# b.net
KiCad netlist of a schematic drawn in EAGLE
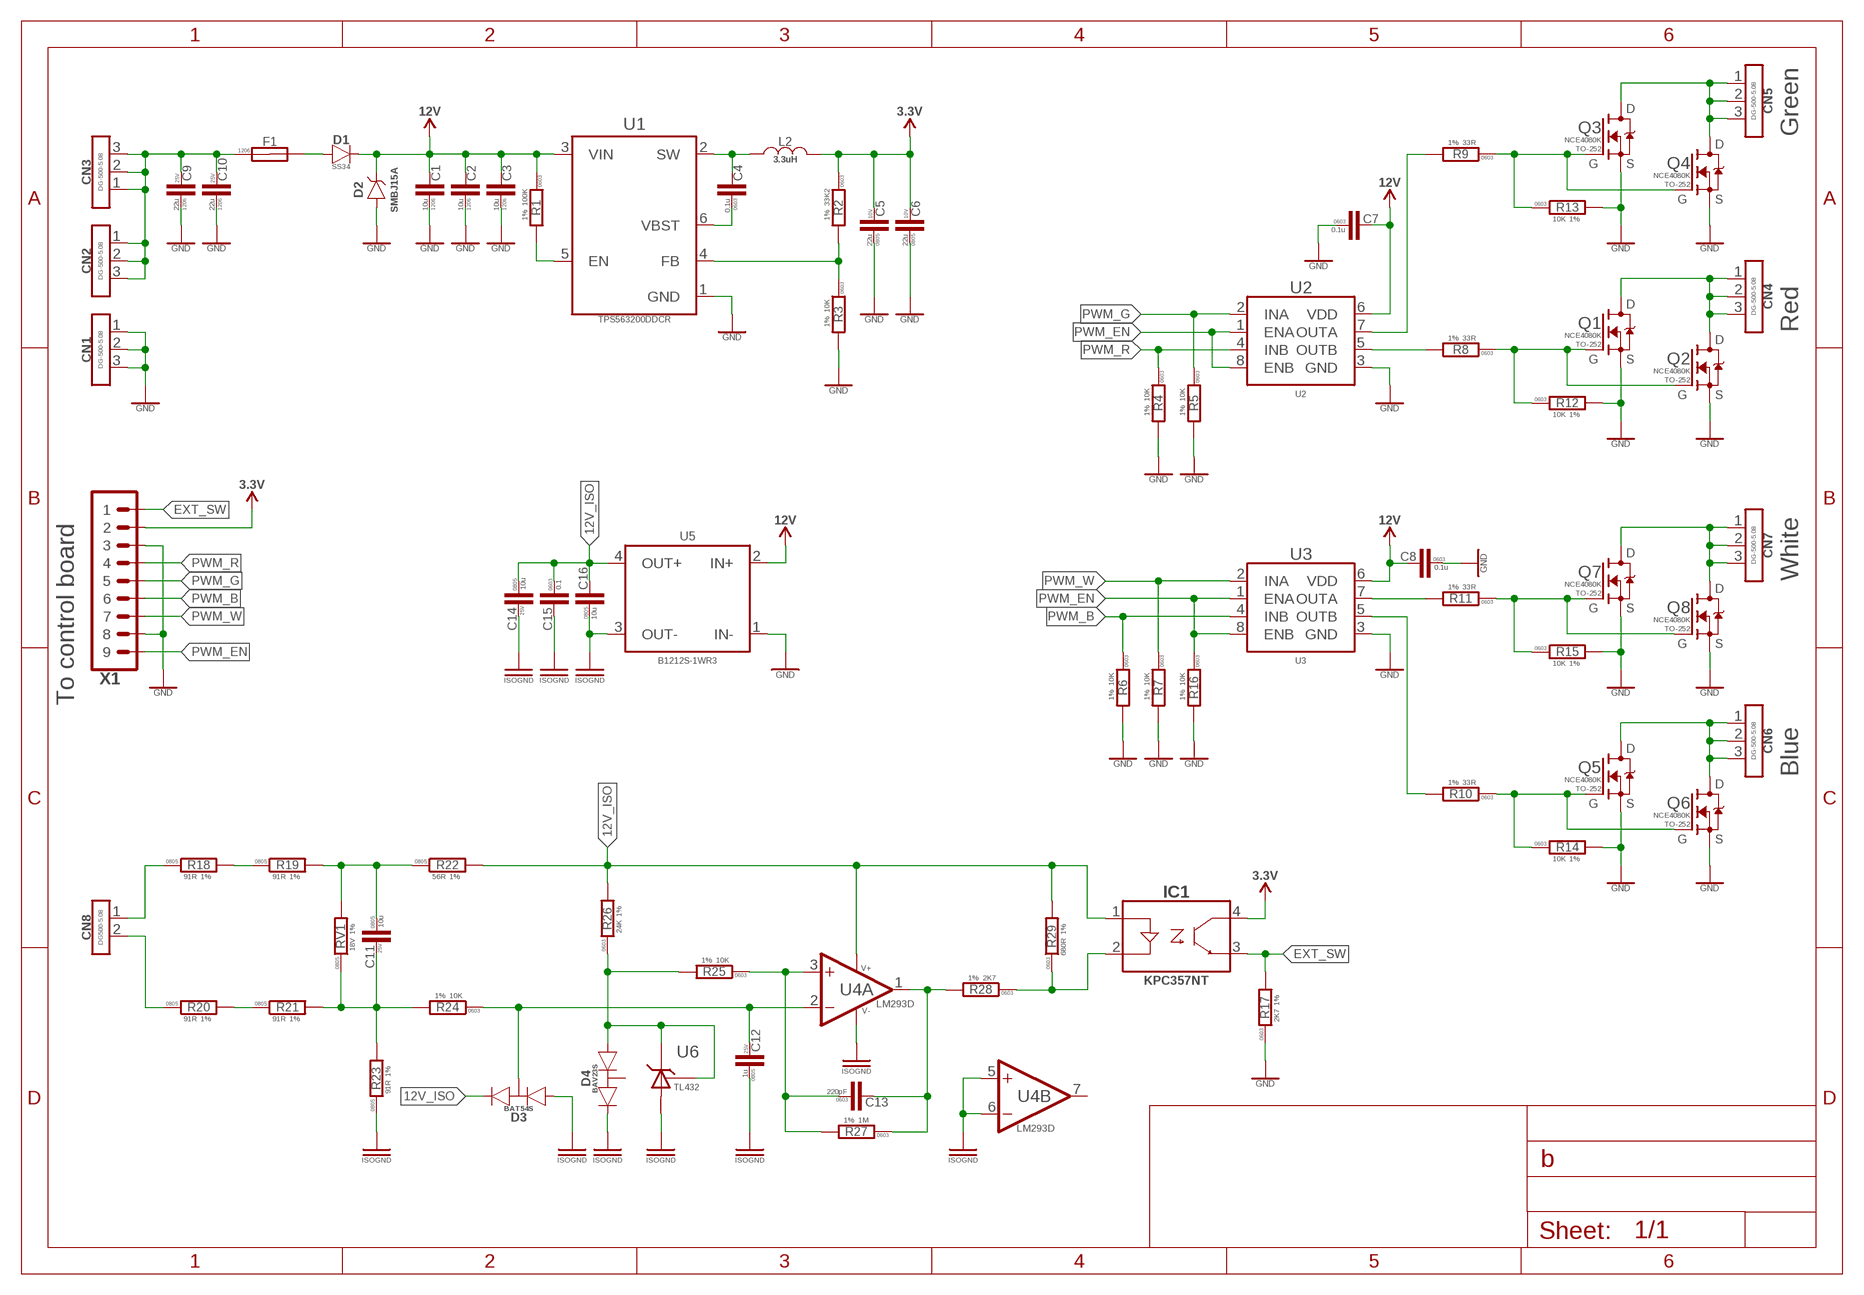
[diagram p0: schematic, sheet 1]

(export (version "E")
  (design (tool "Eeschema 10.0.6"))
  (components
    (comp (ref "C1")
      (value "10u")
      (footprint "eagle-import:C1206")
      (fields (field (name "PACKAGE") "1206"))
      (libsource (lib "eagle-import") (part "C-1206"))
    )
    (comp (ref "C2")
      (value "10u")
      (footprint "eagle-import:C1206")
      (fields (field (name "PACKAGE") "1206"))
      (libsource (lib "eagle-import") (part "C-1206"))
    )
    (comp (ref "C3")
      (value "10u")
      (footprint "eagle-import:C1206")
      (fields (field (name "PACKAGE") "1206"))
      (libsource (lib "eagle-import") (part "C-1206"))
    )
    (comp (ref "C4")
      (value "0.1u")
      (footprint "eagle-import:C0603")
      (fields (field (name "PACKAGE") "0603"))
      (libsource (lib "eagle-import") (part "C-0603"))
    )
    (comp (ref "C5")
      (value "22u")
      (footprint "eagle-import:C0805")
      (fields (field (name "PACKAGE") "0805") (field (name "VOLTAGE") "10V"))
      (libsource (lib "eagle-import") (part "C-0805"))
    )
    (comp (ref "C6")
      (value "22u")
      (footprint "eagle-import:C0805")
      (fields (field (name "PACKAGE") "0805") (field (name "VOLTAGE") "10V"))
      (libsource (lib "eagle-import") (part "C-0805"))
    )
    (comp (ref "C7")
      (value "0.1u")
      (footprint "eagle-import:C0603")
      (fields (field (name "PACKAGE") "0603"))
      (libsource (lib "eagle-import") (part "C-0603"))
    )
    (comp (ref "C8")
      (value "0.1u")
      (footprint "eagle-import:C0603")
      (fields (field (name "PACKAGE") "0603"))
      (libsource (lib "eagle-import") (part "C-0603"))
    )
    (comp (ref "C9")
      (value "22u")
      (footprint "eagle-import:C1206")
      (fields (field (name "PACKAGE") "1206") (field (name "VOLTAGE") "25V"))
      (libsource (lib "eagle-import") (part "C-1206"))
    )
    (comp (ref "C10")
      (value "22u")
      (footprint "eagle-import:C1206")
      (fields (field (name "PACKAGE") "1206") (field (name "VOLTAGE") "25V"))
      (libsource (lib "eagle-import") (part "C-1206"))
    )
    (comp (ref "C11")
      (value "10u")
      (footprint "eagle-import:C0805")
      (fields (field (name "PACKAGE") "0805") (field (name "VOLTAGE") "25V"))
      (libsource (lib "eagle-import") (part "C-0805"))
    )
    (comp (ref "C12")
      (value "1u")
      (footprint "eagle-import:C0805")
      (fields (field (name "PACKAGE") "0805") (field (name "VOLTAGE") "25V"))
      (libsource (lib "eagle-import") (part "C-0805"))
    )
    (comp (ref "C13")
      (value "220pF")
      (footprint "eagle-import:C0603")
      (fields (field (name "PACKAGE") "0603"))
      (libsource (lib "eagle-import") (part "C-0603"))
    )
    (comp (ref "C14")
      (value "10u")
      (footprint "eagle-import:C0805")
      (fields (field (name "PACKAGE") "0805") (field (name "VOLTAGE") "25V"))
      (libsource (lib "eagle-import") (part "C-0805"))
    )
    (comp (ref "C15")
      (value "0.1")
      (footprint "eagle-import:C0603")
      (fields (field (name "PACKAGE") "0603"))
      (libsource (lib "eagle-import") (part "C-0603"))
    )
    (comp (ref "C16")
      (value "10u")
      (footprint "eagle-import:C0805")
      (fields (field (name "PACKAGE") "0805"))
      (libsource (lib "eagle-import") (part "C-0805"))
    )
    (comp (ref "CN1")
      (value "CON-3P-DG500-5.08")
      (footprint "eagle-import:DG500-5.08-03P")
      (fields (field (name "TYPE") "DG-500-5.08") (field (name "MANF") "Degson Electronics"))
      (libsource (lib "eagle-import") (part "CON-3P-DG500-5.08"))
    )
    (comp (ref "CN2")
      (value "CON-3P-DG500-5.08")
      (footprint "eagle-import:DG500-5.08-03P")
      (fields (field (name "TYPE") "DG-500-5.08") (field (name "MANF") "Degson Electronics"))
      (libsource (lib "eagle-import") (part "CON-3P-DG500-5.08"))
    )
    (comp (ref "CN3")
      (value "CON-3P-DG500-5.08")
      (footprint "eagle-import:DG500-5.08-03P")
      (fields (field (name "TYPE") "DG-500-5.08") (field (name "MANF") "Degson Electronics"))
      (libsource (lib "eagle-import") (part "CON-3P-DG500-5.08"))
    )
    (comp (ref "CN4")
      (value "CON-3P-DG500-5.08")
      (footprint "eagle-import:DG500-5.08-03P")
      (fields (field (name "TYPE") "DG-500-5.08") (field (name "MANF") "Degson Electronics"))
      (libsource (lib "eagle-import") (part "CON-3P-DG500-5.08"))
    )
    (comp (ref "CN5")
      (value "CON-3P-DG500-5.08")
      (footprint "eagle-import:DG500-5.08-03P")
      (fields (field (name "TYPE") "DG-500-5.08") (field (name "MANF") "Degson Electronics"))
      (libsource (lib "eagle-import") (part "CON-3P-DG500-5.08"))
    )
    (comp (ref "CN6")
      (value "CON-3P-DG500-5.08")
      (footprint "eagle-import:DG500-5.08-03P")
      (fields (field (name "TYPE") "DG-500-5.08") (field (name "MANF") "Degson Electronics"))
      (libsource (lib "eagle-import") (part "CON-3P-DG500-5.08"))
    )
    (comp (ref "CN7")
      (value "CON-3P-DG500-5.08")
      (footprint "eagle-import:DG500-5.08-03P")
      (fields (field (name "TYPE") "DG-500-5.08") (field (name "MANF") "Degson Electronics"))
      (libsource (lib "eagle-import") (part "CON-3P-DG500-5.08"))
    )
    (comp (ref "CN8")
      (value "DG508V-2P")
      (footprint "eagle-import:DG500-5.08-02P")
      (fields (field (name "TYPE") "DG500-5.08") (field (name "MANF") "Degson Electronics"))
      (libsource (lib "eagle-import") (part "CON-2P-DG500-5.08"))
    )
    (comp (ref "D1")
      (value "SS24")
      (footprint "eagle-import:DO-214AC(SMA)")
      (fields (field (name "MANF#") "SS34") (field (name "MANF") "MDD（Microdiode Electronics）"))
      (libsource (lib "eagle-import") (part "SS34"))
    )
    (comp (ref "D2")
      (value "SMBJ15A-SMB")
      (footprint "eagle-import:DO-214AA(SMB)")
      (fields (field (name "MANF#") "SMBJ15A") (field (name "MANF") "Littelfuse"))
      (libsource (lib "eagle-import") (part "SMBJ15A-SMB"))
    )
    (comp (ref "D3")
      (value "BAT54S")
      (footprint "eagle-import:SOT23")
      (fields (field (name "MANF#") "BAT54S") (field (name "MANF") "NEXPERIA"))
      (libsource (lib "eagle-import") (part "BAT54S-SOT23"))
    )
    (comp (ref "D4")
      (value "BAV23S-SOT23")
      (footprint "eagle-import:SOT23")
      (fields (field (name "MANF#") "BAV23S") (field (name "MANF") "NEXPERIA"))
      (libsource (lib "eagle-import") (part "BAV23S-SOT23"))
    )
    (comp (ref "F1")
      (value "eFUSE-1206-500mA")
      (footprint "eagle-import:F1206")
      (fields (field (name "PACKAGE") "1206"))
      (libsource (lib "eagle-import") (part "FUSE-1206"))
    )
    (comp (ref "IC1")
      (value "KPC357NT-SOP-4")
      (footprint "eagle-import:-SOP-4")
      (fields (field (name "MANF#") "KPC357NT") (field (name "MANF") "COSMO"))
      (libsource (lib "eagle-import") (part "KPC357NT-SOP-4"))
    )
    (comp (ref "L2")
      (value "3.3uH")
      (footprint "eagle-import:SWPA6020")
      (fields (field (name "MANF") "Sunlord"))
      (libsource (lib "eagle-import") (part "3.3µH-SWPA6020"))
    )
    (comp (ref "Q1")
      (value "100N04")
      (footprint "eagle-import:D-PAK")
      (fields (field (name "MANF#") "NCE4080K") (field (name "PACKAGE") "TO-252") (field (name "MANF") "NCE"))
      (libsource (lib "eagle-import") (part "NCE4080K"))
    )
    (comp (ref "Q2")
      (value "100N04")
      (footprint "eagle-import:D-PAK")
      (fields (field (name "MANF#") "NCE4080K") (field (name "PACKAGE") "TO-252") (field (name "MANF") "NCE"))
      (libsource (lib "eagle-import") (part "NCE4080K"))
    )
    (comp (ref "Q3")
      (value "100N04")
      (footprint "eagle-import:D-PAK")
      (fields (field (name "MANF#") "NCE4080K") (field (name "PACKAGE") "TO-252") (field (name "MANF") "NCE"))
      (libsource (lib "eagle-import") (part "NCE4080K"))
    )
    (comp (ref "Q4")
      (value "100N04")
      (footprint "eagle-import:D-PAK")
      (fields (field (name "MANF#") "NCE4080K") (field (name "PACKAGE") "TO-252") (field (name "MANF") "NCE"))
      (libsource (lib "eagle-import") (part "NCE4080K"))
    )
    (comp (ref "Q5")
      (value "100N04")
      (footprint "eagle-import:D-PAK")
      (fields (field (name "MANF#") "NCE4080K") (field (name "PACKAGE") "TO-252") (field (name "MANF") "NCE"))
      (libsource (lib "eagle-import") (part "NCE4080K"))
    )
    (comp (ref "Q6")
      (value "100N04")
      (footprint "eagle-import:D-PAK")
      (fields (field (name "MANF#") "NCE4080K") (field (name "PACKAGE") "TO-252") (field (name "MANF") "NCE"))
      (libsource (lib "eagle-import") (part "NCE4080K"))
    )
    (comp (ref "Q7")
      (value "100N04")
      (footprint "eagle-import:D-PAK")
      (fields (field (name "MANF#") "NCE4080K") (field (name "PACKAGE") "TO-252") (field (name "MANF") "NCE"))
      (libsource (lib "eagle-import") (part "NCE4080K"))
    )
    (comp (ref "Q8")
      (value "100N04")
      (footprint "eagle-import:D-PAK")
      (fields (field (name "MANF#") "NCE4080K") (field (name "PACKAGE") "TO-252") (field (name "MANF") "NCE"))
      (libsource (lib "eagle-import") (part "NCE4080K"))
    )
    (comp (ref "R1")
      (value "100K")
      (footprint "eagle-import:R0603")
      (fields (field (name "PACKAGE") "0603") (field (name "TOLERANCE") "1%"))
      (libsource (lib "eagle-import") (part "R-0603-1%"))
    )
    (comp (ref "R2")
      (value "33K2")
      (footprint "eagle-import:R0603")
      (fields (field (name "PACKAGE") "0603") (field (name "TOLERANCE") "1%"))
      (libsource (lib "eagle-import") (part "R-0603-1%"))
    )
    (comp (ref "R3")
      (value "10K")
      (footprint "eagle-import:R0603")
      (fields (field (name "PACKAGE") "0603") (field (name "TOLERANCE") "1%"))
      (libsource (lib "eagle-import") (part "R-0603-1%"))
    )
    (comp (ref "R4")
      (value "10K")
      (footprint "eagle-import:R0603")
      (fields (field (name "PACKAGE") "0603") (field (name "TOLERANCE") "1%"))
      (libsource (lib "eagle-import") (part "R-0603-1%"))
    )
    (comp (ref "R5")
      (value "10K")
      (footprint "eagle-import:R0603")
      (fields (field (name "PACKAGE") "0603") (field (name "TOLERANCE") "1%"))
      (libsource (lib "eagle-import") (part "R-0603-1%"))
    )
    (comp (ref "R6")
      (value "10K")
      (footprint "eagle-import:R0603")
      (fields (field (name "PACKAGE") "0603") (field (name "TOLERANCE") "1%"))
      (libsource (lib "eagle-import") (part "R-0603-1%"))
    )
    (comp (ref "R7")
      (value "10K")
      (footprint "eagle-import:R0603")
      (fields (field (name "PACKAGE") "0603") (field (name "TOLERANCE") "1%"))
      (libsource (lib "eagle-import") (part "R-0603-1%"))
    )
    (comp (ref "R8")
      (value "33R")
      (footprint "eagle-import:R0603")
      (fields (field (name "PACKAGE") "0603") (field (name "TOLERANCE") "1%"))
      (libsource (lib "eagle-import") (part "R-0603-1%"))
    )
    (comp (ref "R9")
      (value "33R")
      (footprint "eagle-import:R0603")
      (fields (field (name "PACKAGE") "0603") (field (name "TOLERANCE") "1%"))
      (libsource (lib "eagle-import") (part "R-0603-1%"))
    )
    (comp (ref "R10")
      (value "33R")
      (footprint "eagle-import:R0603")
      (fields (field (name "PACKAGE") "0603") (field (name "TOLERANCE") "1%"))
      (libsource (lib "eagle-import") (part "R-0603-1%"))
    )
    (comp (ref "R11")
      (value "33R")
      (footprint "eagle-import:R0603")
      (fields (field (name "PACKAGE") "0603") (field (name "TOLERANCE") "1%"))
      (libsource (lib "eagle-import") (part "R-0603-1%"))
    )
    (comp (ref "R12")
      (value "10K")
      (footprint "eagle-import:R0603")
      (fields (field (name "PACKAGE") "0603") (field (name "TOLERANCE") "1%"))
      (libsource (lib "eagle-import") (part "R-0603-1%"))
    )
    (comp (ref "R13")
      (value "10K")
      (footprint "eagle-import:R0603")
      (fields (field (name "PACKAGE") "0603") (field (name "TOLERANCE") "1%"))
      (libsource (lib "eagle-import") (part "R-0603-1%"))
    )
    (comp (ref "R14")
      (value "10K")
      (footprint "eagle-import:R0603")
      (fields (field (name "PACKAGE") "0603") (field (name "TOLERANCE") "1%"))
      (libsource (lib "eagle-import") (part "R-0603-1%"))
    )
    (comp (ref "R15")
      (value "10K")
      (footprint "eagle-import:R0603")
      (fields (field (name "PACKAGE") "0603") (field (name "TOLERANCE") "1%"))
      (libsource (lib "eagle-import") (part "R-0603-1%"))
    )
    (comp (ref "R16")
      (value "10K")
      (footprint "eagle-import:R0603")
      (fields (field (name "PACKAGE") "0603") (field (name "TOLERANCE") "1%"))
      (libsource (lib "eagle-import") (part "R-0603-1%"))
    )
    (comp (ref "R17")
      (value "2K7")
      (footprint "eagle-import:R0603")
      (fields (field (name "PACKAGE") "0603") (field (name "TOLERANCE") "1%"))
      (libsource (lib "eagle-import") (part "R-0603-1%"))
    )
    (comp (ref "R18")
      (value "91R")
      (footprint "eagle-import:R0805")
      (fields (field (name "PACKAGE") "0805") (field (name "TOLERANCE") "1%"))
      (libsource (lib "eagle-import") (part "R-0805-1%"))
    )
    (comp (ref "R19")
      (value "91R")
      (footprint "eagle-import:R0805")
      (fields (field (name "PACKAGE") "0805") (field (name "TOLERANCE") "1%"))
      (libsource (lib "eagle-import") (part "R-0805-1%"))
    )
    (comp (ref "R20")
      (value "91R")
      (footprint "eagle-import:R0805")
      (fields (field (name "PACKAGE") "0805") (field (name "TOLERANCE") "1%"))
      (libsource (lib "eagle-import") (part "R-0805-1%"))
    )
    (comp (ref "R21")
      (value "91R")
      (footprint "eagle-import:R0805")
      (fields (field (name "PACKAGE") "0805") (field (name "TOLERANCE") "1%"))
      (libsource (lib "eagle-import") (part "R-0805-1%"))
    )
    (comp (ref "R22")
      (value "56R")
      (footprint "eagle-import:R0805")
      (fields (field (name "PACKAGE") "0805") (field (name "TOLERANCE") "1%"))
      (libsource (lib "eagle-import") (part "R-0805-1%"))
    )
    (comp (ref "R23")
      (value "91R")
      (footprint "eagle-import:R0805")
      (fields (field (name "PACKAGE") "0805") (field (name "TOLERANCE") "1%"))
      (libsource (lib "eagle-import") (part "R-0805-1%"))
    )
    (comp (ref "R24")
      (value "10K")
      (footprint "eagle-import:R0603")
      (fields (field (name "PACKAGE") "0603") (field (name "TOLERANCE") "1%"))
      (libsource (lib "eagle-import") (part "R-0603-1%"))
    )
    (comp (ref "R25")
      (value "10K")
      (footprint "eagle-import:R0603")
      (fields (field (name "PACKAGE") "0603") (field (name "TOLERANCE") "1%"))
      (libsource (lib "eagle-import") (part "R-0603-1%"))
    )
    (comp (ref "R26")
      (value "24K")
      (footprint "eagle-import:R0603")
      (fields (field (name "PACKAGE") "0603") (field (name "TOLERANCE") "1%"))
      (libsource (lib "eagle-import") (part "R-0603-1%"))
    )
    (comp (ref "R27")
      (value "1M")
      (footprint "eagle-import:R0603")
      (fields (field (name "PACKAGE") "0603") (field (name "TOLERANCE") "1%"))
      (libsource (lib "eagle-import") (part "R-0603-1%"))
    )
    (comp (ref "R28")
      (value "2K7")
      (footprint "eagle-import:R0603")
      (fields (field (name "PACKAGE") "0603") (field (name "TOLERANCE") "1%"))
      (libsource (lib "eagle-import") (part "R-0603-1%"))
    )
    (comp (ref "R29")
      (value "680R")
      (footprint "eagle-import:R0603")
      (fields (field (name "PACKAGE") "0603") (field (name "TOLERANCE") "1%"))
      (libsource (lib "eagle-import") (part "R-0603-1%"))
    )
    (comp (ref "RV1")
      (value "18V")
      (footprint "eagle-import:R0805")
      (fields (field (name "PACKAGE") "0805") (field (name "TOLERANCE") "1%"))
      (libsource (lib "eagle-import") (part "R-0805-1%"))
    )
    (comp (ref "U1")
      (value "TPS563200")
      (footprint "eagle-import:SOT23-6")
      (fields (field (name "MANF#") "TPS563200DDCR") (field (name "MANF") "Texas Instruments"))
      (libsource (lib "eagle-import") (part "TPS563200"))
    )
    (comp (ref "U2")
      (value "PN7762S")
      (footprint "eagle-import:SOIC8")
      (fields (field (name "MANF") "Chipown"))
      (libsource (lib "eagle-import") (part "PN7762S"))
    )
    (comp (ref "U3")
      (value "PN7762S")
      (footprint "eagle-import:SOIC8")
      (fields (field (name "MANF") "Chipown"))
      (libsource (lib "eagle-import") (part "PN7762S"))
    )
    (comp (ref "U4")
      (value "LM293D")
      (footprint "eagle-import:SOIC8")
      (fields (field (name "MANF#") "LM293D") (field (name "MANF") "STMicroelectronics"))
      (libsource (lib "eagle-import") (part "LM293D-SO8"))
    )
    (comp (ref "U5")
      (value "B1212S-1WR3")
      (footprint "eagle-import:SIP-4")
      (fields (field (name "MANF#") "B1212S-1WR3") (field (name "MANF") "Mornsun Power"))
      (libsource (lib "eagle-import") (part "B1212S-1WR3"))
    )
    (comp (ref "U6")
      (value "TL432")
      (footprint "eagle-import:SOT23B-3")
      (fields (field (name "MANF#") "TL432") (field (name "MANF") "Texas Instruments"))
      (libsource (lib "eagle-import") (part "TL432"))
    )
    (comp (ref "X1")
      (value "PINHEAD_1X09-2.54-TH-MALE")
      (footprint "eagle-import:1X09-PTH-2.54")
      (libsource (lib "eagle-import") (part "PINHEAD_1X09-2.54-TH-MALE"))
    )
  )
  (nets
    (net (code "1") (name "3.3V") (class "Default")
      (node (ref "C5") (pin "2") (pinfunction "2_2") (pintype "passive"))
      (node (ref "C6") (pin "2") (pinfunction "2_2") (pintype "passive"))
      (node (ref "IC1") (pin "4") (pinfunction "COLLECTOR_4") (pintype "bidirectional"))
      (node (ref "L2") (pin "2") (pinfunction "2_2") (pintype "bidirectional"))
      (node (ref "R2") (pin "1") (pinfunction "1_1") (pintype "passive"))
      (node (ref "X1") (pin "2") (pinfunction "2_2") (pintype "passive"))
    )
    (net (code "2") (name "12V") (class "Default")
      (node (ref "C1") (pin "P$2") (pinfunction "2_P$2") (pintype "passive"))
      (node (ref "C2") (pin "P$2") (pinfunction "2_P$2") (pintype "passive"))
      (node (ref "C3") (pin "P$2") (pinfunction "2_P$2") (pintype "passive"))
      (node (ref "C7") (pin "2") (pinfunction "2_2") (pintype "passive"))
      (node (ref "C8") (pin "2") (pinfunction "2_2") (pintype "passive"))
      (node (ref "D1") (pin "C") (pinfunction "C_C") (pintype "passive"))
      (node (ref "D2") (pin "C") (pinfunction "C_C") (pintype "bidirectional"))
      (node (ref "R1") (pin "1") (pinfunction "1_1") (pintype "passive"))
      (node (ref "U1") (pin "3") (pinfunction "VIN_3") (pintype "bidirectional"))
      (node (ref "U2") (pin "6") (pinfunction "VDD_6") (pintype "passive"))
      (node (ref "U3") (pin "6") (pinfunction "VDD_6") (pintype "passive"))
      (node (ref "U5") (pin "2") (pinfunction "IN+_2") (pintype "bidirectional"))
    )
    (net (code "3") (name "12V_ISO") (class "Default")
      (node (ref "C14") (pin "1") (pinfunction "1_1") (pintype "passive"))
      (node (ref "C15") (pin "1") (pinfunction "1_1") (pintype "passive"))
      (node (ref "C16") (pin "2") (pinfunction "2_2") (pintype "passive"))
      (node (ref "D3") (pin "2") (pinfunction "C_2") (pintype "passive"))
      (node (ref "IC1") (pin "1") (pinfunction "A_1") (pintype "bidirectional"))
      (node (ref "R22") (pin "2") (pinfunction "2_2") (pintype "passive"))
      (node (ref "R26") (pin "2") (pinfunction "2_2") (pintype "passive"))
      (node (ref "R29") (pin "2") (pinfunction "2_2") (pintype "passive"))
      (node (ref "U4") (pin "8") (pinfunction "V+_8") (pintype "power_in"))
      (node (ref "U5") (pin "4") (pinfunction "OUT+_4") (pintype "bidirectional"))
    )
    (net (code "4") (name "EXT_SW") (class "Default")
      (node (ref "IC1") (pin "3") (pinfunction "EMITTER_3") (pintype "bidirectional"))
      (node (ref "R17") (pin "2") (pinfunction "2_2") (pintype "passive"))
      (node (ref "X1") (pin "1") (pinfunction "1_1") (pintype "passive"))
    )
    (net (code "5") (name "GND") (class "Default")
      (node (ref "C1") (pin "P$1") (pinfunction "1_P$1") (pintype "passive"))
      (node (ref "C10") (pin "P$1") (pinfunction "1_P$1") (pintype "passive"))
      (node (ref "C2") (pin "P$1") (pinfunction "1_P$1") (pintype "passive"))
      (node (ref "C3") (pin "P$1") (pinfunction "1_P$1") (pintype "passive"))
      (node (ref "C5") (pin "1") (pinfunction "1_1") (pintype "passive"))
      (node (ref "C6") (pin "1") (pinfunction "1_1") (pintype "passive"))
      (node (ref "C7") (pin "1") (pinfunction "1_1") (pintype "passive"))
      (node (ref "C8") (pin "1") (pinfunction "1_1") (pintype "passive"))
      (node (ref "C9") (pin "P$1") (pinfunction "1_P$1") (pintype "passive"))
      (node (ref "CN1") (pin "1") (pinfunction "1_1") (pintype "bidirectional"))
      (node (ref "CN1") (pin "2") (pinfunction "2_2") (pintype "bidirectional"))
      (node (ref "CN1") (pin "3") (pinfunction "3_3") (pintype "bidirectional"))
      (node (ref "D2") (pin "A") (pinfunction "A_A") (pintype "bidirectional"))
      (node (ref "Q1") (pin "S") (pinfunction "S_S") (pintype "passive"))
      (node (ref "Q2") (pin "S") (pinfunction "S_S") (pintype "passive"))
      (node (ref "Q3") (pin "S") (pinfunction "S_S") (pintype "passive"))
      (node (ref "Q4") (pin "S") (pinfunction "S_S") (pintype "passive"))
      (node (ref "Q5") (pin "S") (pinfunction "S_S") (pintype "passive"))
      (node (ref "Q6") (pin "S") (pinfunction "S_S") (pintype "passive"))
      (node (ref "Q7") (pin "S") (pinfunction "S_S") (pintype "passive"))
      (node (ref "Q8") (pin "S") (pinfunction "S_S") (pintype "passive"))
      (node (ref "R12") (pin "2") (pinfunction "2_2") (pintype "passive"))
      (node (ref "R13") (pin "2") (pinfunction "2_2") (pintype "passive"))
      (node (ref "R14") (pin "2") (pinfunction "2_2") (pintype "passive"))
      (node (ref "R15") (pin "2") (pinfunction "2_2") (pintype "passive"))
      (node (ref "R16") (pin "2") (pinfunction "2_2") (pintype "passive"))
      (node (ref "R17") (pin "1") (pinfunction "1_1") (pintype "passive"))
      (node (ref "R3") (pin "2") (pinfunction "2_2") (pintype "passive"))
      (node (ref "R4") (pin "2") (pinfunction "2_2") (pintype "passive"))
      (node (ref "R5") (pin "2") (pinfunction "2_2") (pintype "passive"))
      (node (ref "R6") (pin "2") (pinfunction "2_2") (pintype "passive"))
      (node (ref "R7") (pin "2") (pinfunction "2_2") (pintype "passive"))
      (node (ref "U1") (pin "1") (pinfunction "GND_1") (pintype "bidirectional"))
      (node (ref "U2") (pin "3") (pinfunction "GND_3") (pintype "passive"))
      (node (ref "U3") (pin "3") (pinfunction "GND_3") (pintype "passive"))
      (node (ref "U5") (pin "1") (pinfunction "IN-_1") (pintype "bidirectional"))
      (node (ref "X1") (pin "3") (pinfunction "3_3") (pintype "passive"))
      (node (ref "X1") (pin "8") (pinfunction "8_8") (pintype "passive"))
    )
    (net (code "6") (name "ISOGND") (class "Default")
      (node (ref "C12") (pin "1") (pinfunction "1_1") (pintype "passive"))
      (node (ref "C14") (pin "2") (pinfunction "2_2") (pintype "passive"))
      (node (ref "C15") (pin "2") (pinfunction "2_2") (pintype "passive"))
      (node (ref "C16") (pin "1") (pinfunction "1_1") (pintype "passive"))
      (node (ref "D3") (pin "1") (pinfunction "A_1") (pintype "passive"))
      (node (ref "D4") (pin "2") (pinfunction "C_2") (pintype "passive"))
      (node (ref "R23") (pin "1") (pinfunction "1_1") (pintype "passive"))
      (node (ref "U4") (pin "4") (pinfunction "V-_4") (pintype "power_in"))
      (node (ref "U4") (pin "5") (pinfunction "IN+_5") (pintype "input"))
      (node (ref "U4") (pin "6") (pinfunction "IN-_6") (pintype "input"))
      (node (ref "U5") (pin "3") (pinfunction "OUT-_3") (pintype "bidirectional"))
      (node (ref "U6") (pin "3") (pinfunction "A_3") (pintype "passive"))
    )
    (net (code "7") (name "Net-(C10-2)") (class "Default")
      (node (ref "C10") (pin "P$2") (pinfunction "2_P$2") (pintype "passive"))
      (node (ref "C9") (pin "P$2") (pinfunction "2_P$2") (pintype "passive"))
      (node (ref "CN2") (pin "1") (pinfunction "1_1") (pintype "bidirectional"))
      (node (ref "CN2") (pin "2") (pinfunction "2_2") (pintype "bidirectional"))
      (node (ref "CN2") (pin "3") (pinfunction "3_3") (pintype "bidirectional"))
      (node (ref "CN3") (pin "1") (pinfunction "1_1") (pintype "bidirectional"))
      (node (ref "CN3") (pin "2") (pinfunction "2_2") (pintype "bidirectional"))
      (node (ref "CN3") (pin "3") (pinfunction "3_3") (pintype "bidirectional"))
      (node (ref "F1") (pin "P$1") (pinfunction "1_P$1") (pintype "passive"))
    )
    (net (code "8") (name "Net-(C11-Pad1)") (class "Default")
      (node (ref "C11") (pin "1") (pinfunction "1_1") (pintype "passive"))
      (node (ref "R19") (pin "2") (pinfunction "2_2") (pintype "passive"))
      (node (ref "R22") (pin "1") (pinfunction "1_1") (pintype "passive"))
      (node (ref "RV1") (pin "2") (pinfunction "2_2") (pintype "passive"))
    )
    (net (code "9") (name "Net-(C11-Pad2)") (class "Default")
      (node (ref "C11") (pin "2") (pinfunction "2_2") (pintype "passive"))
      (node (ref "R21") (pin "2") (pinfunction "2_2") (pintype "passive"))
      (node (ref "R23") (pin "2") (pinfunction "2_2") (pintype "passive"))
      (node (ref "R24") (pin "2") (pinfunction "2_2") (pintype "passive"))
      (node (ref "RV1") (pin "1") (pinfunction "1_1") (pintype "passive"))
    )
    (net (code "10") (name "Net-(CN4-Pad1)") (class "Default")
      (node (ref "CN4") (pin "1") (pinfunction "1_1") (pintype "bidirectional"))
      (node (ref "CN4") (pin "2") (pinfunction "2_2") (pintype "bidirectional"))
      (node (ref "CN4") (pin "3") (pinfunction "3_3") (pintype "bidirectional"))
      (node (ref "Q1") (pin "D") (pinfunction "D_D") (pintype "passive"))
      (node (ref "Q2") (pin "D") (pinfunction "D_D") (pintype "passive"))
    )
    (net (code "11") (name "Net-(CN5-Pad1)") (class "Default")
      (node (ref "CN5") (pin "1") (pinfunction "1_1") (pintype "bidirectional"))
      (node (ref "CN5") (pin "2") (pinfunction "2_2") (pintype "bidirectional"))
      (node (ref "CN5") (pin "3") (pinfunction "3_3") (pintype "bidirectional"))
      (node (ref "Q3") (pin "D") (pinfunction "D_D") (pintype "passive"))
      (node (ref "Q4") (pin "D") (pinfunction "D_D") (pintype "passive"))
    )
    (net (code "12") (name "Net-(CN6-Pad1)") (class "Default")
      (node (ref "CN6") (pin "1") (pinfunction "1_1") (pintype "bidirectional"))
      (node (ref "CN6") (pin "2") (pinfunction "2_2") (pintype "bidirectional"))
      (node (ref "CN6") (pin "3") (pinfunction "3_3") (pintype "bidirectional"))
      (node (ref "Q5") (pin "D") (pinfunction "D_D") (pintype "passive"))
      (node (ref "Q6") (pin "D") (pinfunction "D_D") (pintype "passive"))
    )
    (net (code "13") (name "Net-(CN7-Pad1)") (class "Default")
      (node (ref "CN7") (pin "1") (pinfunction "1_1") (pintype "bidirectional"))
      (node (ref "CN7") (pin "2") (pinfunction "2_2") (pintype "bidirectional"))
      (node (ref "CN7") (pin "3") (pinfunction "3_3") (pintype "bidirectional"))
      (node (ref "Q7") (pin "D") (pinfunction "D_D") (pintype "passive"))
      (node (ref "Q8") (pin "D") (pinfunction "D_D") (pintype "passive"))
    )
    (net (code "14") (name "Net-(CN8-Pad1)") (class "Default")
      (node (ref "CN8") (pin "1") (pinfunction "1_1") (pintype "bidirectional"))
      (node (ref "R18") (pin "1") (pinfunction "1_1") (pintype "passive"))
    )
    (net (code "15") (name "Net-(CN8-Pad2)") (class "Default")
      (node (ref "CN8") (pin "2") (pinfunction "2_2") (pintype "bidirectional"))
      (node (ref "R20") (pin "1") (pinfunction "1_1") (pintype "passive"))
    )
    (net (code "16") (name "Net-(D3-COMMON)") (class "Default")
      (node (ref "C12") (pin "2") (pinfunction "2_2") (pintype "passive"))
      (node (ref "D3") (pin "3") (pinfunction "COMMON_3") (pintype "bidirectional"))
      (node (ref "R24") (pin "1") (pinfunction "1_1") (pintype "passive"))
      (node (ref "U4") (pin "2") (pinfunction "IN-_2") (pintype "input"))
    )
    (net (code "17") (name "Net-(D4-A)") (class "Default")
      (node (ref "D4") (pin "1") (pinfunction "A_1") (pintype "passive"))
      (node (ref "R25") (pin "2") (pinfunction "2_2") (pintype "passive"))
      (node (ref "R26") (pin "1") (pinfunction "1_1") (pintype "passive"))
      (node (ref "U6") (pin "1") (pinfunction "R_1") (pintype "passive"))
      (node (ref "U6") (pin "2") (pinfunction "C_2") (pintype "passive"))
    )
    (net (code "18") (name "Net-(F1-2)") (class "Default")
      (node (ref "D1") (pin "A") (pinfunction "A_A") (pintype "passive"))
      (node (ref "F1") (pin "P$2") (pinfunction "2_P$2") (pintype "passive"))
    )
    (net (code "19") (name "Net-(IC1-C)") (class "Default")
      (node (ref "IC1") (pin "2") (pinfunction "C_2") (pintype "bidirectional"))
      (node (ref "R28") (pin "1") (pinfunction "1_1") (pintype "passive"))
      (node (ref "R29") (pin "1") (pinfunction "1_1") (pintype "passive"))
    )
    (net (code "20") (name "Net-(Q1-PadG)") (class "Default")
      (node (ref "Q1") (pin "G") (pinfunction "G_G") (pintype "passive"))
      (node (ref "Q2") (pin "G") (pinfunction "G_G") (pintype "passive"))
      (node (ref "R12") (pin "1") (pinfunction "1_1") (pintype "passive"))
      (node (ref "R8") (pin "1") (pinfunction "1_1") (pintype "passive"))
    )
    (net (code "21") (name "Net-(Q3-PadG)") (class "Default")
      (node (ref "Q3") (pin "G") (pinfunction "G_G") (pintype "passive"))
      (node (ref "Q4") (pin "G") (pinfunction "G_G") (pintype "passive"))
      (node (ref "R13") (pin "1") (pinfunction "1_1") (pintype "passive"))
      (node (ref "R9") (pin "1") (pinfunction "1_1") (pintype "passive"))
    )
    (net (code "22") (name "Net-(Q5-PadG)") (class "Default")
      (node (ref "Q5") (pin "G") (pinfunction "G_G") (pintype "passive"))
      (node (ref "Q6") (pin "G") (pinfunction "G_G") (pintype "passive"))
      (node (ref "R10") (pin "1") (pinfunction "1_1") (pintype "passive"))
      (node (ref "R14") (pin "1") (pinfunction "1_1") (pintype "passive"))
    )
    (net (code "23") (name "Net-(Q7-PadG)") (class "Default")
      (node (ref "Q7") (pin "G") (pinfunction "G_G") (pintype "passive"))
      (node (ref "Q8") (pin "G") (pinfunction "G_G") (pintype "passive"))
      (node (ref "R11") (pin "1") (pinfunction "1_1") (pintype "passive"))
      (node (ref "R15") (pin "1") (pinfunction "1_1") (pintype "passive"))
    )
    (net (code "24") (name "Net-(R18-Pad2)") (class "Default")
      (node (ref "R18") (pin "2") (pinfunction "2_2") (pintype "passive"))
      (node (ref "R19") (pin "1") (pinfunction "1_1") (pintype "passive"))
    )
    (net (code "25") (name "Net-(R20-Pad2)") (class "Default")
      (node (ref "R20") (pin "2") (pinfunction "2_2") (pintype "passive"))
      (node (ref "R21") (pin "1") (pinfunction "1_1") (pintype "passive"))
    )
    (net (code "26") (name "Net-(U1-EN)") (class "Default")
      (node (ref "R1") (pin "2") (pinfunction "2_2") (pintype "passive"))
      (node (ref "U1") (pin "5") (pinfunction "EN_5") (pintype "bidirectional"))
    )
    (net (code "27") (name "Net-(U1-FB)") (class "Default")
      (node (ref "R2") (pin "2") (pinfunction "2_2") (pintype "passive"))
      (node (ref "R3") (pin "1") (pinfunction "1_1") (pintype "passive"))
      (node (ref "U1") (pin "4") (pinfunction "FB_4") (pintype "bidirectional"))
    )
    (net (code "28") (name "Net-(U1-SW)") (class "Default")
      (node (ref "C4") (pin "2") (pinfunction "2_2") (pintype "passive"))
      (node (ref "L2") (pin "1") (pinfunction "1_1") (pintype "bidirectional"))
      (node (ref "U1") (pin "2") (pinfunction "SW_2") (pintype "bidirectional"))
    )
    (net (code "29") (name "Net-(U1-VBST)") (class "Default")
      (node (ref "C4") (pin "1") (pinfunction "1_1") (pintype "passive"))
      (node (ref "U1") (pin "6") (pinfunction "VBST_6") (pintype "bidirectional"))
    )
    (net (code "30") (name "Net-(U2-OUTA)") (class "Default")
      (node (ref "R9") (pin "2") (pinfunction "2_2") (pintype "passive"))
      (node (ref "U2") (pin "7") (pinfunction "OUTA_7") (pintype "output"))
    )
    (net (code "31") (name "Net-(U2-OUTB)") (class "Default")
      (node (ref "R8") (pin "2") (pinfunction "2_2") (pintype "passive"))
      (node (ref "U2") (pin "5") (pinfunction "OUTB_5") (pintype "output"))
    )
    (net (code "32") (name "Net-(U3-OUTA)") (class "Default")
      (node (ref "R11") (pin "2") (pinfunction "2_2") (pintype "passive"))
      (node (ref "U3") (pin "7") (pinfunction "OUTA_7") (pintype "output"))
    )
    (net (code "33") (name "Net-(U3-OUTB)") (class "Default")
      (node (ref "R10") (pin "2") (pinfunction "2_2") (pintype "passive"))
      (node (ref "U3") (pin "5") (pinfunction "OUTB_5") (pintype "output"))
    )
    (net (code "34") (name "Net-(U4A-IN+)") (class "Default")
      (node (ref "C13") (pin "1") (pinfunction "1_1") (pintype "passive"))
      (node (ref "R25") (pin "1") (pinfunction "1_1") (pintype "passive"))
      (node (ref "R27") (pin "2") (pinfunction "2_2") (pintype "passive"))
      (node (ref "U4") (pin "3") (pinfunction "IN+_3") (pintype "input"))
    )
    (net (code "35") (name "Net-(U4A-OUT)") (class "Default")
      (node (ref "C13") (pin "2") (pinfunction "2_2") (pintype "passive"))
      (node (ref "R27") (pin "1") (pinfunction "1_1") (pintype "passive"))
      (node (ref "R28") (pin "2") (pinfunction "2_2") (pintype "passive"))
      (node (ref "U4") (pin "1") (pinfunction "OUT_1") (pintype "output"))
    )
    (net (code "36") (name "PWM_B") (class "Default")
      (node (ref "R6") (pin "1") (pinfunction "1_1") (pintype "passive"))
      (node (ref "U3") (pin "4") (pinfunction "INB_4") (pintype "input"))
      (node (ref "X1") (pin "6") (pinfunction "6_6") (pintype "passive"))
    )
    (net (code "37") (name "PWM_EN") (class "Default")
      (node (ref "R16") (pin "1") (pinfunction "1_1") (pintype "passive"))
      (node (ref "U2") (pin "1") (pinfunction "ENA_1") (pintype "input"))
      (node (ref "U2") (pin "8") (pinfunction "ENB_8") (pintype "input"))
      (node (ref "U3") (pin "1") (pinfunction "ENA_1") (pintype "input"))
      (node (ref "U3") (pin "8") (pinfunction "ENB_8") (pintype "input"))
      (node (ref "X1") (pin "9") (pinfunction "9_9") (pintype "passive"))
    )
    (net (code "38") (name "PWM_G") (class "Default")
      (node (ref "R5") (pin "1") (pinfunction "1_1") (pintype "passive"))
      (node (ref "U2") (pin "2") (pinfunction "INA_2") (pintype "input"))
      (node (ref "X1") (pin "5") (pinfunction "5_5") (pintype "passive"))
    )
    (net (code "39") (name "PWM_R") (class "Default")
      (node (ref "R4") (pin "1") (pinfunction "1_1") (pintype "passive"))
      (node (ref "U2") (pin "4") (pinfunction "INB_4") (pintype "input"))
      (node (ref "X1") (pin "4") (pinfunction "4_4") (pintype "passive"))
    )
    (net (code "40") (name "PWM_W") (class "Default")
      (node (ref "R7") (pin "1") (pinfunction "1_1") (pintype "passive"))
      (node (ref "U3") (pin "2") (pinfunction "INA_2") (pintype "input"))
      (node (ref "X1") (pin "7") (pinfunction "7_7") (pintype "passive"))
    )
    (net (code "41") (name "unconnected-(D4-COMMON-Pad3)") (class "Default")
      (node (ref "D4") (pin "3") (pinfunction "COMMON_3") (pintype "bidirectional"))
    )
    (net (code "42") (name "unconnected-(U4B-OUT-Pad7)") (class "Default")
      (node (ref "U4") (pin "7") (pinfunction "OUT_7") (pintype "output"))
    )
  )
)
